# EMI_HV_Protect.net
KiCad netlist of a schematic drawn in Altium Designer
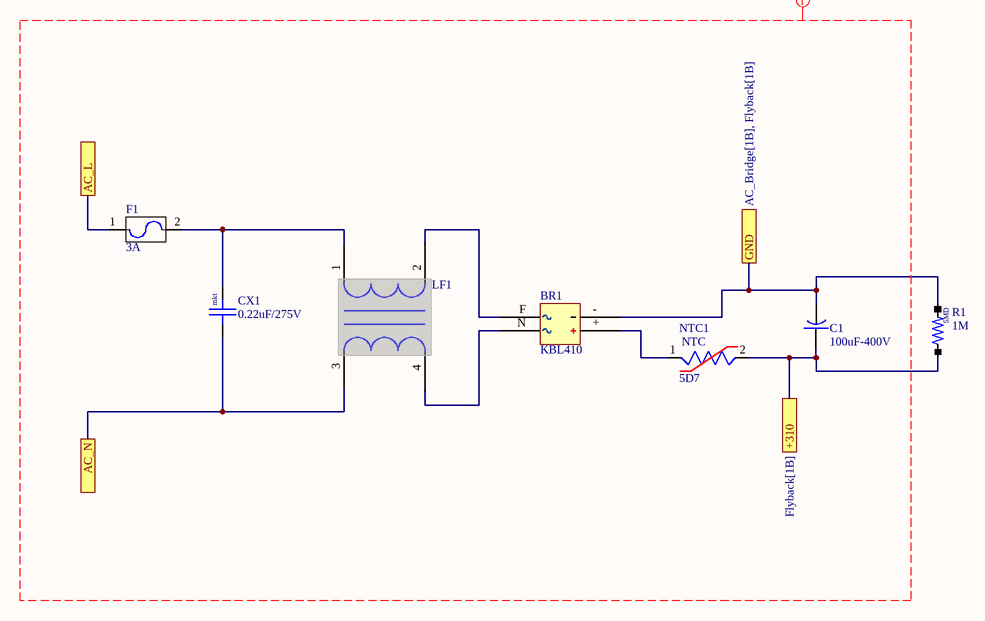
[diagram p0: EMI_HV_Protect.SchDoc]

(export (version "E")
  (design (tool "Eeschema 10.0.6"))
  (components
    (comp (ref "BR1")
      (value "KBL410")
      (footprint "KBP206")
      (libsource (lib "kave-eng-pro") (part "BRIDGE RECTIFIERS"))
    )
    (comp (ref "C1")
      (value "100uF-400V")
      (footprint "CAP-EL-P7MM")
      (libsource (lib "kave-eng-pro") (part "cap-electrolit"))
    )
    (comp (ref "CX1")
      (value "0.22uF/275V")
      (footprint "CAP/0.22uF/275v/mkt")
      (libsource (lib "kave-eng-pro") (part "cap-mkt"))
    )
    (comp (ref "F1")
      (value "3A")
      (footprint "FUZE_GLASS_ISTADE")
      (libsource (lib "kave-eng-pro") (part "fuze"))
    )
    (comp (ref "LF1")
      (value "~")
      (footprint "emi_chok_yd")
      (libsource (lib "kave-eng-pro") (part "emi_chok_yd"))
    )
    (comp (ref "NTC1") (value "5D7") (footprint "NTC_XD_7") (libsource (lib "kave-eng-pro") (part "NTC")))
    (comp (ref "R1") (value "1M") (footprint "RES/1206") (libsource (lib "kave-eng-pro") (part "RES/SMD")))
  )
  (nets
    (net (code "1") (name "/+310") (class "Default")
      (node (ref "C1") (pin "+") (pintype "passive"))
      (node (ref "NTC1") (pin "2") (pinfunction "2_2") (pintype "passive"))
      (node (ref "R1") (pin "1") (pinfunction "1_1") (pintype "passive"))
    )
    (net (code "2") (name "/AC_L") (class "Default") (node (ref "F1") (pin "1") (pintype "passive")))
    (net (code "3") (name "/AC_N") (class "Default")
      (node (ref "CX1") (pin "1") (pintype "passive"))
      (node (ref "LF1") (pin "3") (pintype "passive"))
    )
    (net (code "4") (name "/GND") (class "Default")
      (node (ref "BR1") (pin "-") (pintype "power_in"))
      (node (ref "C1") (pin "-") (pintype "passive"))
      (node (ref "R1") (pin "2") (pinfunction "2_2") (pintype "passive"))
    )
    (net (code "5") (name "Net-(BR1-Pad+)") (class "Default")
      (node (ref "BR1") (pin "+") (pintype "power_in"))
      (node (ref "NTC1") (pin "1") (pinfunction "1_1") (pintype "passive"))
    )
    (net (code "6") (name "Net-(BR1-PadF)") (class "Default")
      (node (ref "BR1") (pin "F") (pintype "power_in"))
      (node (ref "LF1") (pin "2") (pintype "passive"))
    )
    (net (code "7") (name "Net-(BR1-PadN)") (class "Default")
      (node (ref "BR1") (pin "N") (pintype "power_in"))
      (node (ref "LF1") (pin "4") (pintype "passive"))
    )
    (net (code "8") (name "Net-(CX1-Pad2)") (class "Default")
      (node (ref "CX1") (pin "2") (pintype "passive"))
      (node (ref "F1") (pin "2") (pintype "passive"))
      (node (ref "LF1") (pin "1") (pintype "passive"))
    )
  )
)
